# MicroMod_SAMD51.net
KiCad netlist of a schematic drawn in EAGLE
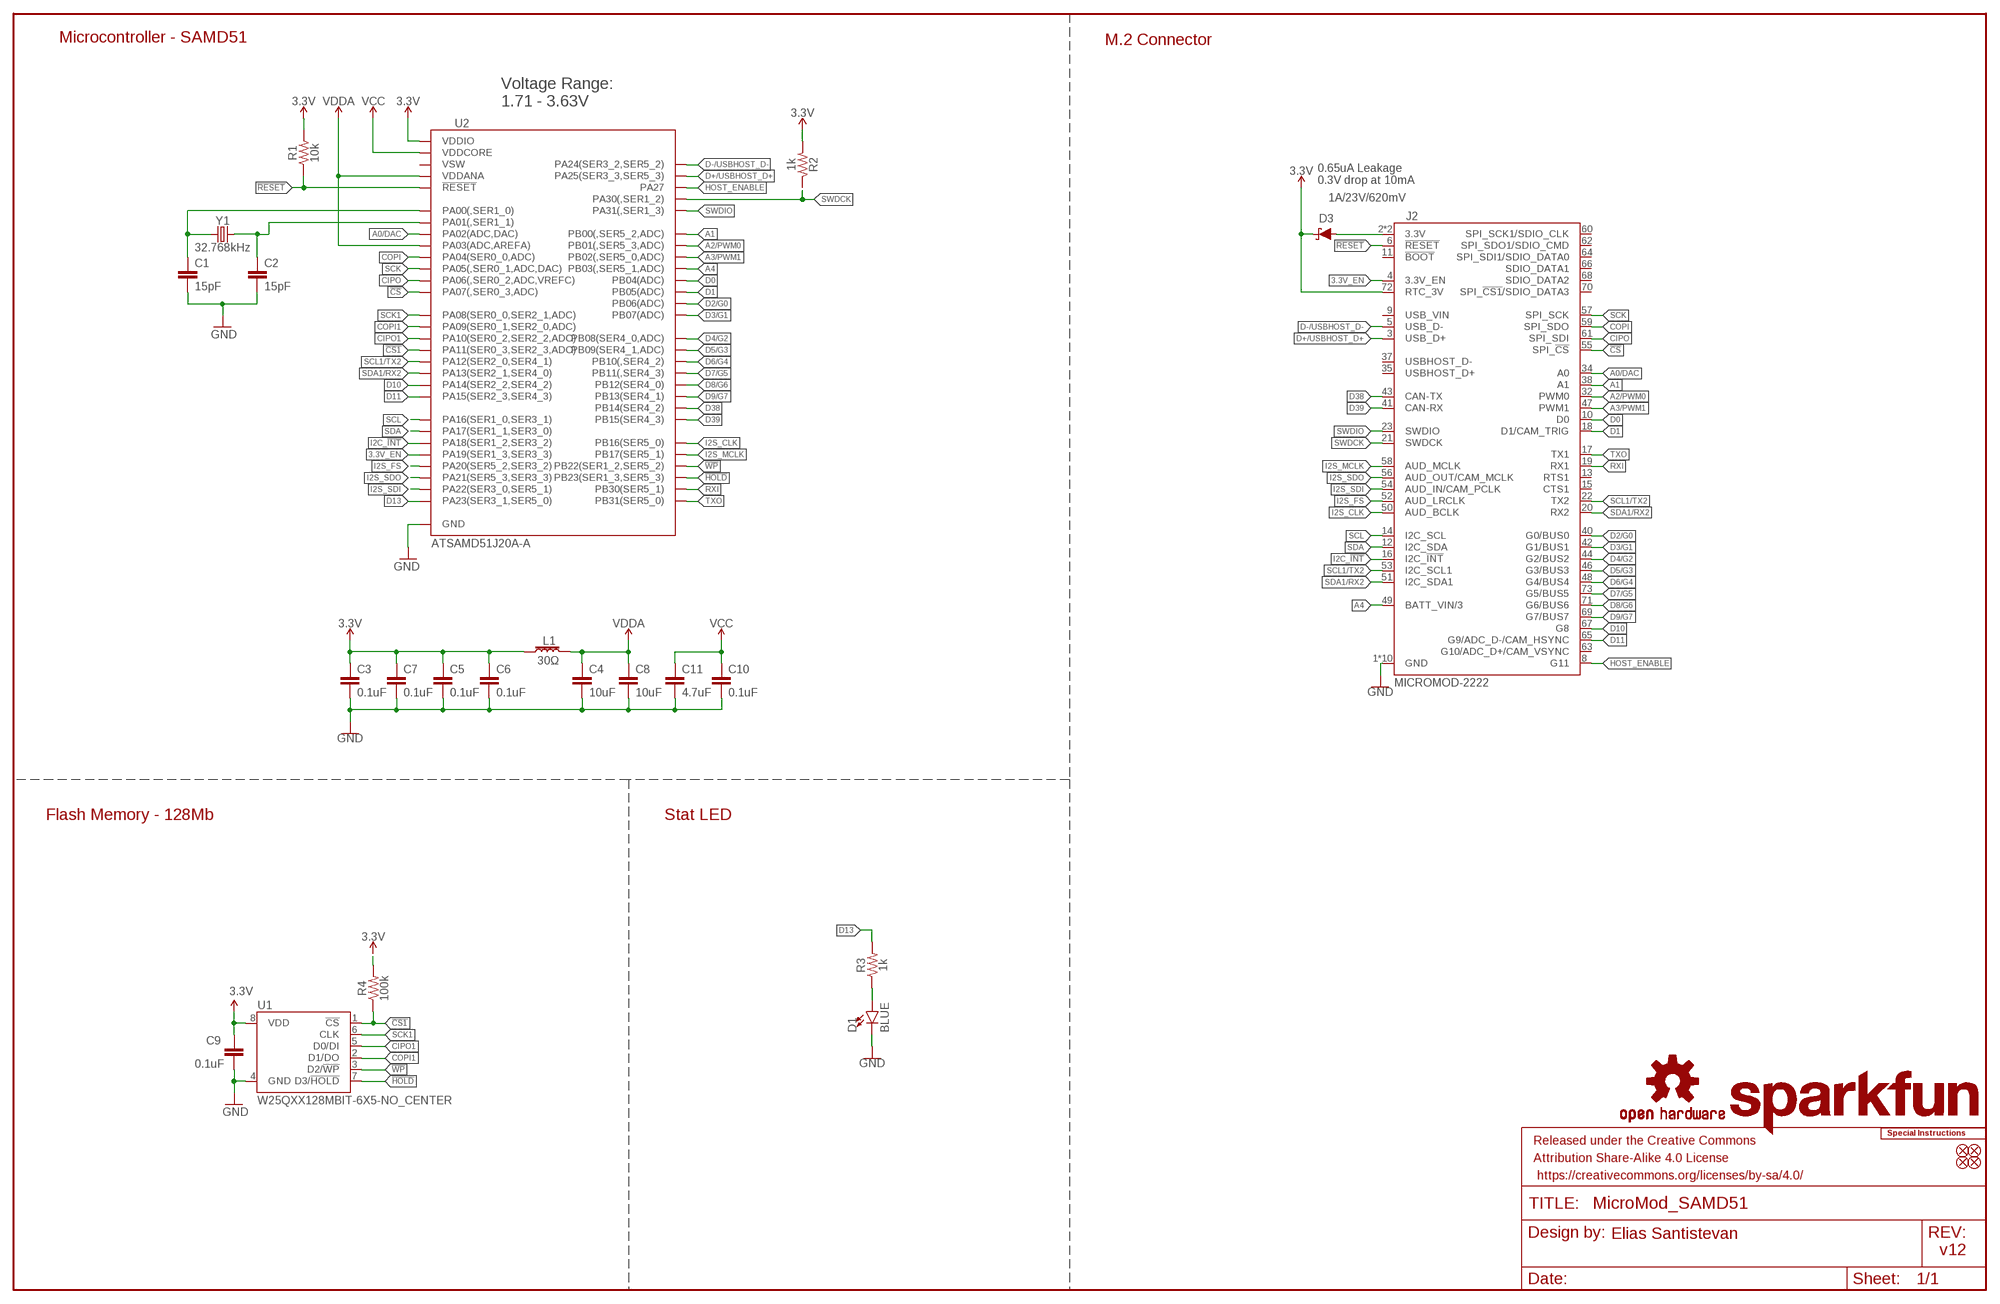
[diagram p0: schematic, sheet 1]

(export (version "E")
  (design (tool "Eeschema 10.0.6"))
  (components
    (comp (ref "C1")
      (value "15pF")
      (footprint "eagle-import:0402-TIGHT")
      (libsource (lib "eagle-import") (part "15PF-0402T-50V-5%"))
    )
    (comp (ref "C2")
      (value "15pF")
      (footprint "eagle-import:0402-TIGHT")
      (libsource (lib "eagle-import") (part "15PF-0402T-50V-5%"))
    )
    (comp (ref "C3")
      (value "0.1uF")
      (footprint "eagle-import:0402-TIGHT")
      (libsource (lib "eagle-import") (part "0.1UF-0402T-10V-10%-X7R"))
    )
    (comp (ref "C4")
      (value "10uF")
      (footprint "eagle-import:0402-TIGHT")
      (libsource (lib "eagle-import") (part "10UF-0402T-6.3V-20%"))
    )
    (comp (ref "C5")
      (value "0.1uF")
      (footprint "eagle-import:0402-TIGHT")
      (libsource (lib "eagle-import") (part "0.1UF-0402T-10V-10%-X7R"))
    )
    (comp (ref "C6")
      (value "0.1uF")
      (footprint "eagle-import:0402-TIGHT")
      (libsource (lib "eagle-import") (part "0.1UF-0402T-10V-10%-X7R"))
    )
    (comp (ref "C7")
      (value "0.1uF")
      (footprint "eagle-import:0402-TIGHT")
      (libsource (lib "eagle-import") (part "0.1UF-0402T-10V-10%-X7R"))
    )
    (comp (ref "C8")
      (value "10uF")
      (footprint "eagle-import:0402-TIGHT")
      (libsource (lib "eagle-import") (part "10UF-0402T-6.3V-20%"))
    )
    (comp (ref "C9")
      (value "0.1uF")
      (footprint "eagle-import:0402-TIGHT")
      (libsource (lib "eagle-import") (part "0.1UF-0402T-10V-10%-X7R"))
    )
    (comp (ref "C10")
      (value "0.1uF")
      (footprint "eagle-import:0402-TIGHT")
      (libsource (lib "eagle-import") (part "0.1UF-0402T-10V-10%-X7R"))
    )
    (comp (ref "C11")
      (value "4.7uF")
      (footprint "eagle-import:0402-TIGHT")
      (libsource (lib "eagle-import") (part "4.7UF-0402_TIGHT-6.3V-20%-X5R"))
    )
    (comp (ref "D1")
      (value "BLUE")
      (footprint "eagle-import:LED-0603")
      (libsource (lib "eagle-import") (part "LED-BLUE0603"))
    )
    (comp (ref "D3")
      (value "1A/23V/620mV")
      (footprint "eagle-import:SOD-323")
      (libsource (lib "eagle-import") (part "DIODE-SCHOTTKY-BAT20J"))
    )
    (comp (ref "FD5")
      (value "FIDUCIALUFIDUCIAL")
      (footprint "eagle-import:FIDUCIAL-MICRO")
      (libsource (lib "eagle-import") (part "FIDUCIALUFIDUCIAL"))
    )
    (comp (ref "FD6")
      (value "FIDUCIALUFIDUCIAL")
      (footprint "eagle-import:FIDUCIAL-MICRO")
      (libsource (lib "eagle-import") (part "FIDUCIALUFIDUCIAL"))
    )
    (comp (ref "FD7")
      (value "FIDUCIALUFIDUCIAL")
      (footprint "eagle-import:FIDUCIAL-MICRO")
      (libsource (lib "eagle-import") (part "FIDUCIALUFIDUCIAL"))
    )
    (comp (ref "FD8")
      (value "FIDUCIALUFIDUCIAL")
      (footprint "eagle-import:FIDUCIAL-MICRO")
      (libsource (lib "eagle-import") (part "FIDUCIALUFIDUCIAL"))
    )
    (comp (ref "FRAME2")
      (value "FRAME-LEDGER")
      (footprint "eagle-import:CREATIVE_COMMONS")
      (libsource (lib "eagle-import") (part "FRAME-LEDGER"))
    )
    (comp (ref "J2")
      (value "MICROMOD-2222")
      (footprint "eagle-import:M.2-CARD-E-22")
      (libsource (lib "eagle-import") (part "MICROMOD-2222"))
    )
    (comp (ref "L1")
      (value "30Ω")
      (footprint "eagle-import:0402-TIGHT")
      (libsource (lib "eagle-import") (part "FERRITE_BEAD-0402-30OHM-100MHZ"))
    )
    (comp (ref "LOGO2")
      (value "OSHW-LOGOMINI")
      (footprint "eagle-import:OSHW-LOGO-MINI")
      (libsource (lib "eagle-import") (part "OSHW-LOGOMINI"))
    )
    (comp (ref "LOGO5")
      (value "SPECIAL_INSTRUCTIONS-ORDERING")
      (footprint "eagle-import:ORDERING_INSTRUCTIONS")
      (libsource (lib "eagle-import") (part "SPECIAL_INSTRUCTIONS-ORDERING"))
    )
    (comp (ref "LOGO6")
      (value "SFE_LOGO_NAME.1_INCH")
      (footprint "eagle-import:SFE_LOGO_NAME_.1")
      (libsource (lib "eagle-import") (part "SFE_LOGO_NAME.1_INCH"))
    )
    (comp (ref "R1")
      (value "10k")
      (footprint "eagle-import:0402-TIGHT")
      (libsource (lib "eagle-import") (part "10KOHM-0402T-1/16W-1%"))
    )
    (comp (ref "R2")
      (value "1k")
      (footprint "eagle-import:0402-TIGHT")
      (libsource (lib "eagle-import") (part "1KOHM-0402T-1/16W-1%"))
    )
    (comp (ref "R3")
      (value "1k")
      (footprint "eagle-import:0402-TIGHT")
      (libsource (lib "eagle-import") (part "1KOHM-0402T-1/16W-1%"))
    )
    (comp (ref "R4")
      (value "100k")
      (footprint "eagle-import:0402-TIGHT")
      (libsource (lib "eagle-import") (part "100KOHM-0402T-1/16W-1%"))
    )
    (comp (ref "U1")
      (value "W25QXX128MBIT-6X5-NO_CENTER")
      (footprint "eagle-import:WSON-8-6X5-NO_CENTERPAD")
      (libsource (lib "eagle-import") (part "W25QXX128MBIT-6X5-NO_CENTER"))
    )
    (comp (ref "U2")
      (value "ATSAMD51J20A-A")
      (footprint "eagle-import:TQFP64")
      (libsource (lib "eagle-import") (part "ATSAMD51J20A-A"))
    )
    (comp (ref "Y1")
      (value "32.768kHz")
      (footprint "eagle-import:CRYSTAL-SMD-3.2X1.5MM")
      (libsource (lib "eagle-import") (part "CRYSTAL-32.768KHZSMD-3.2X1.5"))
    )
  )
  (nets
    (net (code "1") (name "/I2C_~{INT}") (class "Default")
      (node (ref "J2") (pin "16") (pinfunction "I2C_~{INT}_16") (pintype "bidirectional"))
      (node (ref "U2") (pin "37") (pinfunction "PA18(SER1_2,SER3_2)_37") (pintype "bidirectional"))
    )
    (net (code "2") (name "/~{CS1}") (class "Default")
      (node (ref "R4") (pin "1") (pinfunction "1_1") (pintype "passive"))
      (node (ref "U1") (pin "1") (pinfunction "~{CS}_1") (pintype "bidirectional"))
      (node (ref "U2") (pin "20") (pinfunction "PA11(SER0_3,SER2_3,ADC)_20") (pintype "bidirectional"))
    )
    (net (code "3") (name "/~{CS}") (class "Default")
      (node (ref "J2") (pin "55") (pinfunction "SPI_~{CS}_55") (pintype "bidirectional"))
      (node (ref "U2") (pin "16") (pinfunction "PA07(,SER0_3,ADC)_16") (pintype "bidirectional"))
    )
    (net (code "4") (name "/~{HOLD}") (class "Default")
      (node (ref "U1") (pin "7") (pinfunction "D3/~{HOLD}_7") (pintype "bidirectional"))
      (node (ref "U2") (pin "50") (pinfunction "PB23(SER1_3,SER5_3)_50") (pintype "bidirectional"))
    )
    (net (code "5") (name "/~{RESET}") (class "Default")
      (node (ref "J2") (pin "6") (pinfunction "~{RESET}_6") (pintype "bidirectional"))
      (node (ref "R1") (pin "1") (pinfunction "1_1") (pintype "passive"))
      (node (ref "U2") (pin "52") (pinfunction "~{RESET}_52") (pintype "bidirectional"))
    )
    (net (code "6") (name "/~{WP}") (class "Default")
      (node (ref "U1") (pin "3") (pinfunction "D2/~{WP}_3") (pintype "bidirectional"))
      (node (ref "U2") (pin "49") (pinfunction "PB22(SER1_2,SER5_2)_49") (pintype "bidirectional"))
    )
    (net (code "7") (name "3.3V") (class "Default")
      (node (ref "C3") (pin "1") (pinfunction "1_1") (pintype "passive"))
      (node (ref "C5") (pin "1") (pinfunction "1_1") (pintype "passive"))
      (node (ref "C6") (pin "1") (pinfunction "1_1") (pintype "passive"))
      (node (ref "C7") (pin "1") (pinfunction "1_1") (pintype "passive"))
      (node (ref "C9") (pin "1") (pinfunction "1_1") (pintype "passive"))
      (node (ref "D3") (pin "C") (pinfunction "C_C") (pintype "passive"))
      (node (ref "J2") (pin "72") (pinfunction "RTC_3V_72") (pintype "bidirectional"))
      (node (ref "L1") (pin "1") (pinfunction "1_1") (pintype "passive"))
      (node (ref "R1") (pin "2") (pinfunction "2_2") (pintype "passive"))
      (node (ref "R2") (pin "2") (pinfunction "2_2") (pintype "passive"))
      (node (ref "R4") (pin "2") (pinfunction "2_2") (pintype "passive"))
      (node (ref "U1") (pin "8") (pinfunction "VDD_8") (pintype "bidirectional"))
      (node (ref "U2") (pin "21") (pinfunction "VDDIO_21") (pintype "bidirectional"))
      (node (ref "U2") (pin "34") (pinfunction "VDDIO_34") (pintype "bidirectional"))
      (node (ref "U2") (pin "48") (pinfunction "VDDIO_48") (pintype "bidirectional"))
      (node (ref "U2") (pin "56") (pinfunction "VDDIO_56") (pintype "bidirectional"))
    )
    (net (code "8") (name "3.3V_EN") (class "Default")
      (node (ref "J2") (pin "4") (pinfunction "3.3V_EN_4") (pintype "bidirectional"))
      (node (ref "U2") (pin "38") (pinfunction "PA19(SER1_3,SER3_3)_38") (pintype "bidirectional"))
    )
    (net (code "9") (name "A0{slash}DAC") (class "Default")
      (node (ref "J2") (pin "34") (pinfunction "A0_34") (pintype "bidirectional"))
      (node (ref "U2") (pin "3") (pinfunction "PA02(ADC,DAC)_3") (pintype "bidirectional"))
    )
    (net (code "10") (name "A1") (class "Default")
      (node (ref "J2") (pin "38") (pinfunction "A1_38") (pintype "bidirectional"))
      (node (ref "U2") (pin "61") (pinfunction "PB00(,SER5_2,ADC)_61") (pintype "bidirectional"))
    )
    (net (code "11") (name "A2{slash}PWM0") (class "Default")
      (node (ref "J2") (pin "32") (pinfunction "PWM0_32") (pintype "bidirectional"))
      (node (ref "U2") (pin "62") (pinfunction "PB01(,SER5_3,ADC)_62") (pintype "bidirectional"))
    )
    (net (code "12") (name "A3{slash}PWM1") (class "Default")
      (node (ref "J2") (pin "47") (pinfunction "PWM1_47") (pintype "bidirectional"))
      (node (ref "U2") (pin "63") (pinfunction "PB02(,SER5_0,ADC)_63") (pintype "bidirectional"))
    )
    (net (code "13") (name "A4") (class "Default")
      (node (ref "J2") (pin "49") (pinfunction "BATT_VIN/3_49") (pintype "bidirectional"))
      (node (ref "U2") (pin "64") (pinfunction "PB03(,SER5_1,ADC)_64") (pintype "bidirectional"))
    )
    (net (code "14") (name "CIPO") (class "Default")
      (node (ref "J2") (pin "61") (pinfunction "SPI_SDI_61") (pintype "bidirectional"))
      (node (ref "U2") (pin "15") (pinfunction "PA06(,SER0_2,ADC,VREFC)_15") (pintype "bidirectional"))
    )
    (net (code "15") (name "CIPO1") (class "Default")
      (node (ref "U1") (pin "5") (pinfunction "D0/DI_5") (pintype "bidirectional"))
      (node (ref "U2") (pin "19") (pinfunction "PA10(SER0_2,SER2_2,ADC)_19") (pintype "bidirectional"))
    )
    (net (code "16") (name "COPI") (class "Default")
      (node (ref "J2") (pin "59") (pinfunction "SPI_SDO_59") (pintype "bidirectional"))
      (node (ref "U2") (pin "13") (pinfunction "PA04(SER0_0,ADC)_13") (pintype "bidirectional"))
    )
    (net (code "17") (name "COPI1") (class "Default")
      (node (ref "U1") (pin "2") (pinfunction "D1/DO_2") (pintype "bidirectional"))
      (node (ref "U2") (pin "18") (pinfunction "PA09(SER0_1,SER2_0,ADC)_18") (pintype "bidirectional"))
    )
    (net (code "18") (name "D+{slash}USBHOST_D+") (class "Default")
      (node (ref "J2") (pin "3") (pinfunction "USB_D+_3") (pintype "bidirectional"))
      (node (ref "U2") (pin "46") (pinfunction "PA25(SER3_3,SER5_3)_46") (pintype "bidirectional"))
    )
    (net (code "19") (name "D-{slash}USBHOST_D-") (class "Default")
      (node (ref "J2") (pin "5") (pinfunction "USB_D-_5") (pintype "bidirectional"))
      (node (ref "U2") (pin "45") (pinfunction "PA24(SER3_2,SER5_2)_45") (pintype "bidirectional"))
    )
    (net (code "20") (name "D0") (class "Default")
      (node (ref "J2") (pin "10") (pinfunction "D0_10") (pintype "bidirectional"))
      (node (ref "U2") (pin "5") (pinfunction "PB04(ADC)_5") (pintype "bidirectional"))
    )
    (net (code "21") (name "D1") (class "Default")
      (node (ref "J2") (pin "18") (pinfunction "D1/CAM_TRIG_18") (pintype "bidirectional"))
      (node (ref "U2") (pin "6") (pinfunction "PB05(ADC)_6") (pintype "bidirectional"))
    )
    (net (code "22") (name "D2{slash}G0") (class "Default")
      (node (ref "J2") (pin "40") (pinfunction "G0/BUS0_40") (pintype "bidirectional"))
      (node (ref "U2") (pin "9") (pinfunction "PB06(ADC)_9") (pintype "bidirectional"))
    )
    (net (code "23") (name "D3{slash}G1") (class "Default")
      (node (ref "J2") (pin "42") (pinfunction "G1/BUS1_42") (pintype "bidirectional"))
      (node (ref "U2") (pin "10") (pinfunction "PB07(ADC)_10") (pintype "bidirectional"))
    )
    (net (code "24") (name "D4{slash}G2") (class "Default")
      (node (ref "J2") (pin "44") (pinfunction "G2/BUS2_44") (pintype "bidirectional"))
      (node (ref "U2") (pin "11") (pinfunction "PB08(SER4_0,ADC)_11") (pintype "bidirectional"))
    )
    (net (code "25") (name "D5{slash}G3") (class "Default")
      (node (ref "J2") (pin "46") (pinfunction "G3/BUS3_46") (pintype "bidirectional"))
      (node (ref "U2") (pin "12") (pinfunction "PB09(SER4_1,ADC)_12") (pintype "bidirectional"))
    )
    (net (code "26") (name "D6{slash}G4") (class "Default")
      (node (ref "J2") (pin "48") (pinfunction "G4/BUS4_48") (pintype "bidirectional"))
      (node (ref "U2") (pin "23") (pinfunction "PB10(,SER4_2)_23") (pintype "bidirectional"))
    )
    (net (code "27") (name "D7{slash}G5") (class "Default")
      (node (ref "J2") (pin "73") (pinfunction "G5/BUS5_73") (pintype "bidirectional"))
      (node (ref "U2") (pin "24") (pinfunction "PB11(,SER4_3)_24") (pintype "bidirectional"))
    )
    (net (code "28") (name "D8{slash}G6") (class "Default")
      (node (ref "J2") (pin "71") (pinfunction "G6/BUS6_71") (pintype "bidirectional"))
      (node (ref "U2") (pin "25") (pinfunction "PB12(SER4_0)_25") (pintype "bidirectional"))
    )
    (net (code "29") (name "D9{slash}G7") (class "Default")
      (node (ref "J2") (pin "69") (pinfunction "G7/BUS7_69") (pintype "bidirectional"))
      (node (ref "U2") (pin "26") (pinfunction "PB13(SER4_1)_26") (pintype "bidirectional"))
    )
    (net (code "30") (name "D10") (class "Default")
      (node (ref "J2") (pin "67") (pinfunction "G8_67") (pintype "bidirectional"))
      (node (ref "U2") (pin "31") (pinfunction "PA14(SER2_2,SER4_2)_31") (pintype "bidirectional"))
    )
    (net (code "31") (name "D11") (class "Default")
      (node (ref "J2") (pin "65") (pinfunction "G9/ADC_D-/CAM_HSYNC_65") (pintype "bidirectional"))
      (node (ref "U2") (pin "32") (pinfunction "PA15(SER2_3,SER4_3)_32") (pintype "bidirectional"))
    )
    (net (code "32") (name "D13") (class "Default")
      (node (ref "R3") (pin "2") (pinfunction "2_2") (pintype "passive"))
      (node (ref "U2") (pin "44") (pinfunction "PA23(SER3_1,SER5_0)_44") (pintype "bidirectional"))
    )
    (net (code "33") (name "D38") (class "Default")
      (node (ref "J2") (pin "43") (pinfunction "CAN-TX_43") (pintype "bidirectional"))
      (node (ref "U2") (pin "27") (pinfunction "PB14(SER4_2)_27") (pintype "bidirectional"))
    )
    (net (code "34") (name "D39") (class "Default")
      (node (ref "J2") (pin "41") (pinfunction "CAN-RX_41") (pintype "bidirectional"))
      (node (ref "U2") (pin "28") (pinfunction "PB15(SER4_3)_28") (pintype "bidirectional"))
    )
    (net (code "35") (name "GND") (class "Default")
      (node (ref "C1") (pin "2") (pinfunction "2_2") (pintype "passive"))
      (node (ref "C10") (pin "2") (pinfunction "2_2") (pintype "passive"))
      (node (ref "C11") (pin "2") (pinfunction "2_2") (pintype "passive"))
      (node (ref "C2") (pin "2") (pinfunction "2_2") (pintype "passive"))
      (node (ref "C3") (pin "2") (pinfunction "2_2") (pintype "passive"))
      (node (ref "C4") (pin "2") (pinfunction "2_2") (pintype "passive"))
      (node (ref "C5") (pin "2") (pinfunction "2_2") (pintype "passive"))
      (node (ref "C6") (pin "2") (pinfunction "2_2") (pintype "passive"))
      (node (ref "C7") (pin "2") (pinfunction "2_2") (pintype "passive"))
      (node (ref "C8") (pin "2") (pinfunction "2_2") (pintype "passive"))
      (node (ref "C9") (pin "2") (pinfunction "2_2") (pintype "passive"))
      (node (ref "D1") (pin "C") (pinfunction "C_C") (pintype "passive"))
      (node (ref "J2") (pin "1") (pinfunction "GND_1") (pintype "bidirectional"))
      (node (ref "J2") (pin "33") (pinfunction "GND_33") (pintype "bidirectional"))
      (node (ref "J2") (pin "36") (pinfunction "GND_36") (pintype "bidirectional"))
      (node (ref "J2") (pin "39") (pinfunction "GND_39") (pintype "bidirectional"))
      (node (ref "J2") (pin "45") (pinfunction "GND_45") (pintype "bidirectional"))
      (node (ref "J2") (pin "7") (pinfunction "GND_7") (pintype "bidirectional"))
      (node (ref "J2") (pin "75") (pinfunction "GND_75") (pintype "bidirectional"))
      (node (ref "J2") (pin "GND1") (pinfunction "GND_GND1") (pintype "bidirectional"))
      (node (ref "J2") (pin "GND2") (pinfunction "GND_GND2") (pintype "bidirectional"))
      (node (ref "J2") (pin "GND3") (pinfunction "GND_GND3") (pintype "bidirectional"))
      (node (ref "U1") (pin "4") (pinfunction "GND_4") (pintype "bidirectional"))
      (node (ref "U2") (pin "22") (pinfunction "GND_22") (pintype "bidirectional"))
      (node (ref "U2") (pin "33") (pinfunction "GND_33") (pintype "bidirectional"))
      (node (ref "U2") (pin "47") (pinfunction "GND_47") (pintype "bidirectional"))
      (node (ref "U2") (pin "54") (pinfunction "GND_54") (pintype "bidirectional"))
      (node (ref "U2") (pin "7") (pinfunction "GND_7") (pintype "bidirectional"))
    )
    (net (code "36") (name "HOST_ENABLE") (class "Default")
      (node (ref "J2") (pin "8") (pinfunction "G11_8") (pintype "bidirectional"))
      (node (ref "U2") (pin "51") (pinfunction "PA27_51") (pintype "bidirectional"))
    )
    (net (code "37") (name "I2S_CLK") (class "Default")
      (node (ref "J2") (pin "50") (pinfunction "AUD_BCLK_50") (pintype "bidirectional"))
      (node (ref "U2") (pin "39") (pinfunction "PB16(SER5_0)_39") (pintype "bidirectional"))
    )
    (net (code "38") (name "I2S_FS") (class "Default")
      (node (ref "J2") (pin "52") (pinfunction "AUD_LRCLK_52") (pintype "bidirectional"))
      (node (ref "U2") (pin "41") (pinfunction "PA20(SER5_2,SER3_2)_41") (pintype "bidirectional"))
    )
    (net (code "39") (name "I2S_MCLK") (class "Default")
      (node (ref "J2") (pin "58") (pinfunction "AUD_MCLK_58") (pintype "bidirectional"))
      (node (ref "U2") (pin "40") (pinfunction "PB17(SER5_1)_40") (pintype "bidirectional"))
    )
    (net (code "40") (name "I2S_SDI") (class "Default")
      (node (ref "J2") (pin "54") (pinfunction "AUD_IN/CAM_PCLK_54") (pintype "bidirectional"))
      (node (ref "U2") (pin "43") (pinfunction "PA22(SER3_0,SER5_1)_43") (pintype "bidirectional"))
    )
    (net (code "41") (name "I2S_SDO") (class "Default")
      (node (ref "J2") (pin "56") (pinfunction "AUD_OUT/CAM_MCLK_56") (pintype "bidirectional"))
      (node (ref "U2") (pin "42") (pinfunction "PA21(SER5_3,SER3_3)_42") (pintype "bidirectional"))
    )
    (net (code "42") (name "Net-(D1-PadA)") (class "Default")
      (node (ref "D1") (pin "A") (pinfunction "A_A") (pintype "passive"))
      (node (ref "R3") (pin "1") (pinfunction "1_1") (pintype "passive"))
    )
    (net (code "43") (name "Net-(D3-PadA)") (class "Default")
      (node (ref "D3") (pin "A") (pinfunction "A_A") (pintype "passive"))
      (node (ref "J2") (pin "2") (pinfunction "3.3V_2") (pintype "bidirectional"))
      (node (ref "J2") (pin "74") (pinfunction "3.3V_74") (pintype "bidirectional"))
    )
    (net (code "44") (name "Net-(U2-PA00(,SER1_0))") (class "Default")
      (node (ref "C1") (pin "1") (pinfunction "1_1") (pintype "passive"))
      (node (ref "U2") (pin "1") (pinfunction "PA00(,SER1_0)_1") (pintype "bidirectional"))
      (node (ref "Y1") (pin "P$1") (pinfunction "1_P$1") (pintype "passive"))
    )
    (net (code "45") (name "Net-(U2-PA01(,SER1_1))") (class "Default")
      (node (ref "C2") (pin "1") (pinfunction "1_1") (pintype "passive"))
      (node (ref "U2") (pin "2") (pinfunction "PA01(,SER1_1)_2") (pintype "bidirectional"))
      (node (ref "Y1") (pin "P$2") (pinfunction "2_P$2") (pintype "passive"))
    )
    (net (code "46") (name "RXI") (class "Default")
      (node (ref "J2") (pin "19") (pinfunction "RX1_19") (pintype "bidirectional"))
      (node (ref "U2") (pin "59") (pinfunction "PB30(SER5_1)_59") (pintype "bidirectional"))
    )
    (net (code "47") (name "SCK") (class "Default")
      (node (ref "J2") (pin "57") (pinfunction "SPI_SCK_57") (pintype "bidirectional"))
      (node (ref "U2") (pin "14") (pinfunction "PA05(,SER0_1,ADC,DAC)_14") (pintype "bidirectional"))
    )
    (net (code "48") (name "SCK1") (class "Default")
      (node (ref "U1") (pin "6") (pinfunction "CLK_6") (pintype "bidirectional"))
      (node (ref "U2") (pin "17") (pinfunction "PA08(SER0_0,SER2_1,ADC)_17") (pintype "bidirectional"))
    )
    (net (code "49") (name "SCL") (class "Default")
      (node (ref "J2") (pin "14") (pinfunction "I2C_SCL_14") (pintype "bidirectional"))
      (node (ref "U2") (pin "35") (pinfunction "PA16(SER1_0,SER3_1)_35") (pintype "bidirectional"))
    )
    (net (code "50") (name "SCL1{slash}TX2") (class "Default")
      (node (ref "J2") (pin "22") (pinfunction "TX2_22") (pintype "bidirectional"))
      (node (ref "J2") (pin "53") (pinfunction "I2C_SCL1_53") (pintype "bidirectional"))
      (node (ref "U2") (pin "29") (pinfunction "PA12(SER2_0,SER4_1)_29") (pintype "bidirectional"))
    )
    (net (code "51") (name "SDA") (class "Default")
      (node (ref "J2") (pin "12") (pinfunction "I2C_SDA_12") (pintype "bidirectional"))
      (node (ref "U2") (pin "36") (pinfunction "PA17(SER1_1,SER3_0)_36") (pintype "bidirectional"))
    )
    (net (code "52") (name "SDA1{slash}RX2") (class "Default")
      (node (ref "J2") (pin "20") (pinfunction "RX2_20") (pintype "bidirectional"))
      (node (ref "J2") (pin "51") (pinfunction "I2C_SDA1_51") (pintype "bidirectional"))
      (node (ref "U2") (pin "30") (pinfunction "PA13(SER2_1,SER4_0)_30") (pintype "bidirectional"))
    )
    (net (code "53") (name "SWDCK") (class "Default")
      (node (ref "J2") (pin "21") (pinfunction "SWDCK_21") (pintype "bidirectional"))
      (node (ref "R2") (pin "1") (pinfunction "1_1") (pintype "passive"))
      (node (ref "U2") (pin "57") (pinfunction "PA30(,SER1_2)_57") (pintype "bidirectional"))
    )
    (net (code "54") (name "SWDIO") (class "Default")
      (node (ref "J2") (pin "23") (pinfunction "SWDIO_23") (pintype "bidirectional"))
      (node (ref "U2") (pin "58") (pinfunction "PA31(,SER1_3)_58") (pintype "bidirectional"))
    )
    (net (code "55") (name "TXO") (class "Default")
      (node (ref "J2") (pin "17") (pinfunction "TX1_17") (pintype "bidirectional"))
      (node (ref "U2") (pin "60") (pinfunction "PB31(SER5_0)_60") (pintype "bidirectional"))
    )
    (net (code "56") (name "VCC") (class "Default")
      (node (ref "C10") (pin "1") (pinfunction "1_1") (pintype "passive"))
      (node (ref "C11") (pin "1") (pinfunction "1_1") (pintype "passive"))
      (node (ref "U2") (pin "53") (pinfunction "VDDCORE_53") (pintype "bidirectional"))
    )
    (net (code "57") (name "VDDA") (class "Default")
      (node (ref "C4") (pin "1") (pinfunction "1_1") (pintype "passive"))
      (node (ref "C8") (pin "1") (pinfunction "1_1") (pintype "passive"))
      (node (ref "L1") (pin "2") (pinfunction "2_2") (pintype "passive"))
      (node (ref "U2") (pin "4") (pinfunction "PA03(ADC,AREFA)_4") (pintype "bidirectional"))
      (node (ref "U2") (pin "8") (pinfunction "VDDANA_8") (pintype "bidirectional"))
    )
    (net (code "58") (name "unconnected-(J2-CTS1-Pad15)") (class "Default")
      (node (ref "J2") (pin "15") (pinfunction "CTS1_15") (pintype "bidirectional"))
    )
    (net (code "59") (name "unconnected-(J2-G10{slash}ADC_D+{slash}CAM_VSYNC-Pad63)") (class "Default")
      (node (ref "J2") (pin "63") (pinfunction "G10/ADC_D+/CAM_VSYNC_63") (pintype "bidirectional"))
    )
    (net (code "60") (name "unconnected-(J2-RTS1-Pad13)") (class "Default")
      (node (ref "J2") (pin "13") (pinfunction "RTS1_13") (pintype "bidirectional"))
    )
    (net (code "61") (name "unconnected-(J2-SDIO_DATA1-Pad66)") (class "Default")
      (node (ref "J2") (pin "66") (pinfunction "SDIO_DATA1_66") (pintype "bidirectional"))
    )
    (net (code "62") (name "unconnected-(J2-SDIO_DATA2-Pad68)") (class "Default")
      (node (ref "J2") (pin "68") (pinfunction "SDIO_DATA2_68") (pintype "bidirectional"))
    )
    (net (code "63") (name "unconnected-(J2-SPI_SCK1{slash}SDIO_CLK-Pad60)") (class "Default")
      (node (ref "J2") (pin "60") (pinfunction "SPI_SCK1/SDIO_CLK_60") (pintype "bidirectional"))
    )
    (net (code "64") (name "unconnected-(J2-SPI_SDI1{slash}SDIO_DATA0-Pad64)") (class "Default")
      (node (ref "J2") (pin "64") (pinfunction "SPI_SDI1/SDIO_DATA0_64") (pintype "bidirectional"))
    )
    (net (code "65") (name "unconnected-(J2-SPI_SDO1{slash}SDIO_CMD-Pad62)") (class "Default")
      (node (ref "J2") (pin "62") (pinfunction "SPI_SDO1/SDIO_CMD_62") (pintype "bidirectional"))
    )
    (net (code "66") (name "unconnected-(J2-SPI_~{CS1}{slash}SDIO_DATA3-Pad70)") (class "Default")
      (node (ref "J2") (pin "70") (pinfunction "SPI_~{CS1}/SDIO_DATA3_70") (pintype "bidirectional"))
    )
    (net (code "67") (name "unconnected-(J2-USBHOST_D+-Pad35)") (class "Default")
      (node (ref "J2") (pin "35") (pinfunction "USBHOST_D+_35") (pintype "bidirectional"))
    )
    (net (code "68") (name "unconnected-(J2-USBHOST_D--Pad37)") (class "Default")
      (node (ref "J2") (pin "37") (pinfunction "USBHOST_D-_37") (pintype "bidirectional"))
    )
    (net (code "69") (name "unconnected-(J2-USB_VIN-Pad9)") (class "Default")
      (node (ref "J2") (pin "9") (pinfunction "USB_VIN_9") (pintype "bidirectional"))
    )
    (net (code "70") (name "unconnected-(J2-~{BOOT}-Pad11)") (class "Default")
      (node (ref "J2") (pin "11") (pinfunction "~{BOOT}_11") (pintype "bidirectional"))
    )
    (net (code "71") (name "unconnected-(U2-VSW-Pad55)") (class "Default")
      (node (ref "U2") (pin "55") (pinfunction "VSW_55") (pintype "bidirectional"))
    )
  )
)
